# Hg.net
KiCad netlist of a schematic drawn in Altium Designer
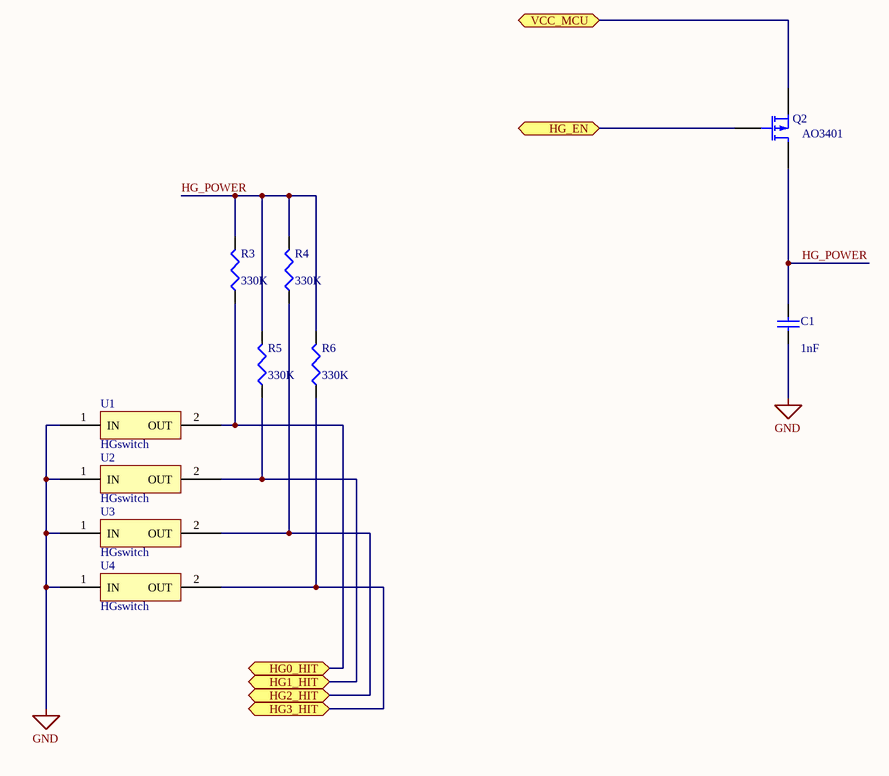
[diagram p0: Hg.SchDoc]

(export (version "E")
  (design (tool "Eeschema 10.0.6"))
  (components
    (comp (ref "C1")
      (value "1nF")
      (footprint "clock:0603")
      (description "Capacitor (Semiconductor SIM Model)")
      (fields (field (name "Comment") "Cap Semi") (field (name "PUBLISHER") "Altium Limited"))
      (libsource (lib "Miscellaneous Devices") (part "Cap Semi"))
    )
    (comp (ref "Q2")
      (value "AO3401")
      (footprint "clock:SOT23-3-PMOS")
      (description "P-Channel MOSFET")
      (fields (field (name "PUBLISHER") "Altium Limited"))
      (libsource (lib "Miscellaneous Devices") (part "MOSFET-P"))
    )
    (comp (ref "R3")
      (value "330K")
      (footprint "clock:0603")
      (description "Resistor")
      (fields (field (name "Comment") "Res3") (field (name "PUBLISHER") "Altium Limited"))
      (libsource (lib "Miscellaneous Devices") (part "Res3"))
    )
    (comp (ref "R4")
      (value "330K")
      (footprint "clock:0603")
      (description "Resistor")
      (fields (field (name "Comment") "Res3") (field (name "PUBLISHER") "Altium Limited"))
      (libsource (lib "Miscellaneous Devices") (part "Res3"))
    )
    (comp (ref "R5")
      (value "330K")
      (footprint "clock:0603")
      (description "Resistor")
      (fields (field (name "Comment") "Res3") (field (name "PUBLISHER") "Altium Limited"))
      (libsource (lib "Miscellaneous Devices") (part "Res3"))
    )
    (comp (ref "R6")
      (value "330K")
      (footprint "clock:0603")
      (description "Resistor")
      (fields (field (name "Comment") "Res3") (field (name "PUBLISHER") "Altium Limited"))
      (libsource (lib "Miscellaneous Devices") (part "Res3"))
    )
    (comp (ref "U1") (value "HGswitch") (footprint "clock:HG-H") (libsource (lib "clock") (part "HGswitch")))
    (comp (ref "U2") (value "HGswitch") (footprint "clock:HG-H") (libsource (lib "clock") (part "HGswitch")))
    (comp (ref "U3") (value "HGswitch") (footprint "clock:HG-H") (libsource (lib "clock") (part "HGswitch")))
    (comp (ref "U4") (value "HGswitch") (footprint "clock:HG-H") (libsource (lib "clock") (part "HGswitch")))
  )
  (nets
    (net (code "1") (name "/HG0_HIT") (class "Default")
      (node (ref "R3") (pin "1") (pinfunction "1_1") (pintype "passive"))
      (node (ref "U1") (pin "2") (pinfunction "OUT_2") (pintype "passive"))
    )
    (net (code "2") (name "/HG1_HIT") (class "Default")
      (node (ref "R5") (pin "1") (pinfunction "1_1") (pintype "passive"))
      (node (ref "U2") (pin "2") (pinfunction "OUT_2") (pintype "passive"))
    )
    (net (code "3") (name "/HG2_HIT") (class "Default")
      (node (ref "R4") (pin "1") (pinfunction "1_1") (pintype "passive"))
      (node (ref "U3") (pin "2") (pinfunction "OUT_2") (pintype "passive"))
    )
    (net (code "4") (name "/HG3_HIT") (class "Default")
      (node (ref "R6") (pin "1") (pinfunction "1_1") (pintype "passive"))
      (node (ref "U4") (pin "2") (pinfunction "OUT_2") (pintype "passive"))
    )
    (net (code "5") (name "/HG_EN") (class "Default")
      (node (ref "Q2") (pin "2") (pinfunction "G_2") (pintype "passive"))
    )
    (net (code "6") (name "/HG_POWER") (class "Default")
      (node (ref "C1") (pin "2") (pinfunction "2_2") (pintype "passive"))
      (node (ref "Q2") (pin "1") (pinfunction "D_1") (pintype "passive"))
      (node (ref "R3") (pin "2") (pinfunction "2_2") (pintype "passive"))
      (node (ref "R4") (pin "2") (pinfunction "2_2") (pintype "passive"))
      (node (ref "R5") (pin "2") (pinfunction "2_2") (pintype "passive"))
      (node (ref "R6") (pin "2") (pinfunction "2_2") (pintype "passive"))
    )
    (net (code "7") (name "/VCC_MCU") (class "Default")
      (node (ref "Q2") (pin "3") (pinfunction "S_3") (pintype "passive"))
    )
    (net (code "8") (name "GND") (class "Default")
      (node (ref "C1") (pin "1") (pinfunction "1_1") (pintype "passive"))
      (node (ref "U1") (pin "1") (pinfunction "IN_1") (pintype "passive"))
      (node (ref "U2") (pin "1") (pinfunction "IN_1") (pintype "passive"))
      (node (ref "U3") (pin "1") (pinfunction "IN_1") (pintype "passive"))
      (node (ref "U4") (pin "1") (pinfunction "IN_1") (pintype "passive"))
    )
  )
)
